# JACart.net
KiCad netlist of a schematic drawn in EAGLE
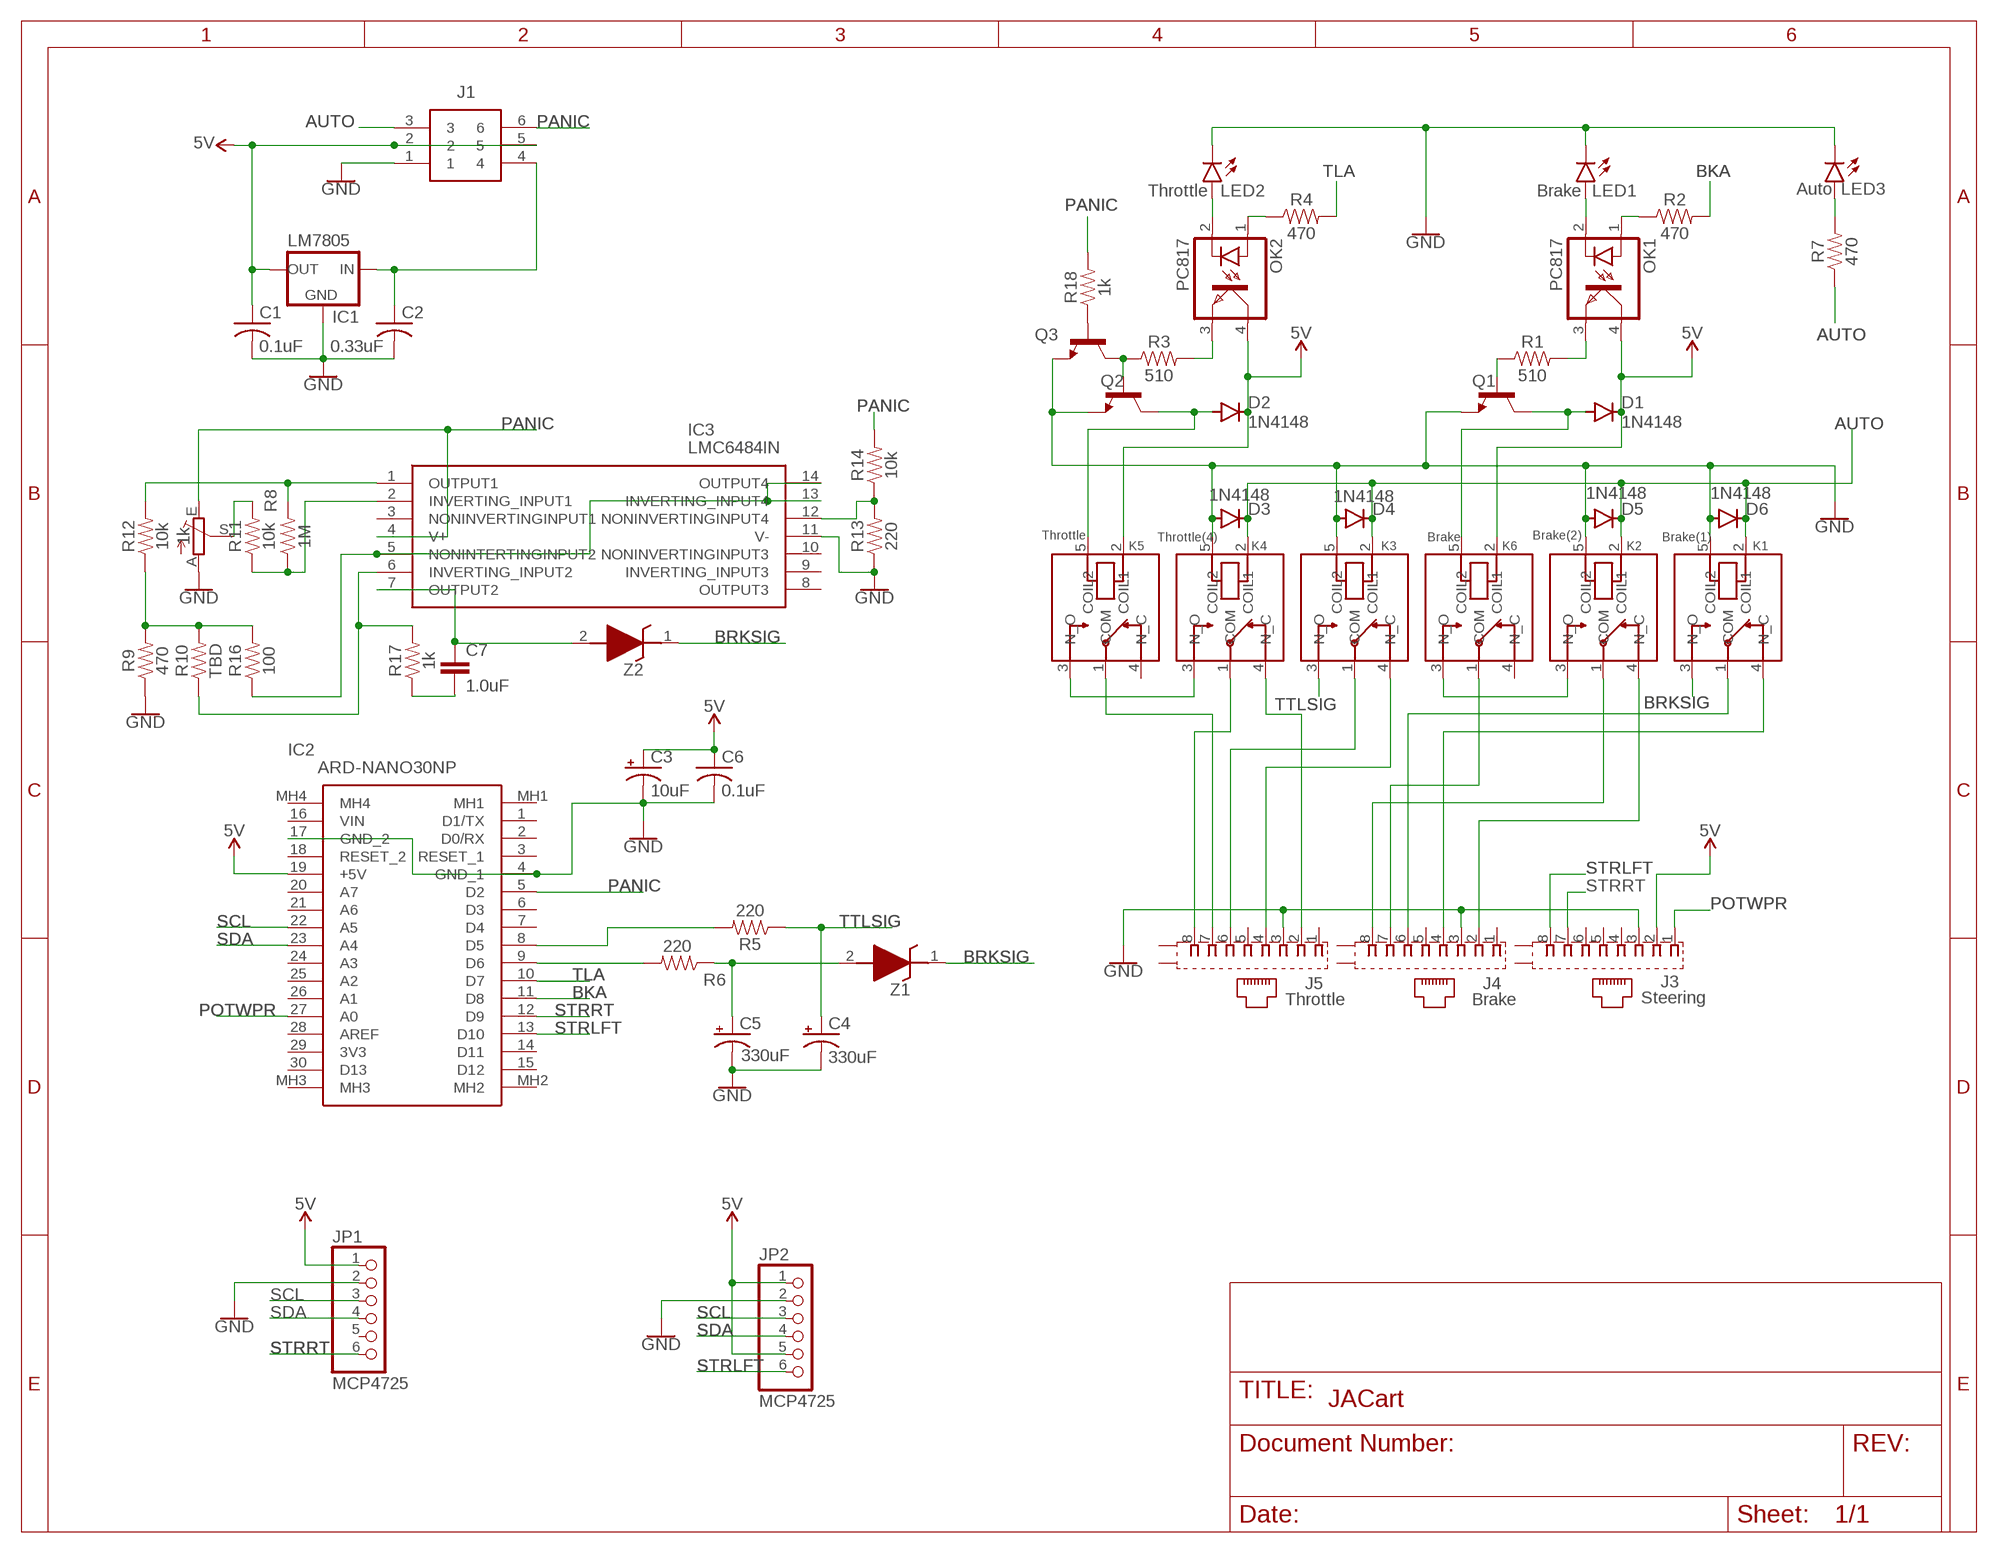
[diagram p0: schematic, sheet 1]

(export (version "E")
  (design (tool "Eeschema 10.0.6"))
  (components
    (comp (ref "C1")
      (value "0.1uF")
      (footprint "eagle-import:C050-024X044")
      (libsource (lib "eagle-import") (part "C-US050-024X044"))
    )
    (comp (ref "C2")
      (value "0.33uF")
      (footprint "eagle-import:C050-024X044")
      (libsource (lib "eagle-import") (part "C-US050-024X044"))
    )
    (comp (ref "C3")
      (value "10uF")
      (footprint "eagle-import:CPOL-RADIAL-2.5MM-5MM")
      (libsource (lib "eagle-import") (part "10UF-POLAR-RADIAL-2.5MM-25V-20%"))
    )
    (comp (ref "C4")
      (value "330uF")
      (footprint "eagle-import:PANASONIC_A")
      (libsource (lib "eagle-import") (part "330UF-PA"))
    )
    (comp (ref "C5")
      (value "330uF")
      (footprint "eagle-import:PANASONIC_A")
      (libsource (lib "eagle-import") (part "330UF-PA"))
    )
    (comp (ref "C6")
      (value "0.1uF")
      (footprint "eagle-import:C050-024X044")
      (fields (field (name "C6") "0.1uF"))
      (libsource (lib "eagle-import") (part "C-US050-024X044"))
    )
    (comp (ref "C7")
      (value "1.0uF")
      (footprint "eagle-import:CAP-PTH-SMALL-KIT")
      (libsource (lib "eagle-import") (part "0.1UF-KIT-EZ-50V-20%"))
    )
    (comp (ref "D1")
      (value "1N4148")
      (footprint "eagle-import:DO35-7")
      (libsource (lib "eagle-import") (part "1N4148DO35-7"))
    )
    (comp (ref "D2")
      (value "1N4148")
      (footprint "eagle-import:DO35-7")
      (libsource (lib "eagle-import") (part "1N4148DO35-7"))
    )
    (comp (ref "D3")
      (value "1N4148")
      (footprint "eagle-import:DO35-7")
      (libsource (lib "eagle-import") (part "1N4148DO35-7"))
    )
    (comp (ref "D4")
      (value "1N4148")
      (footprint "eagle-import:DO35-7")
      (libsource (lib "eagle-import") (part "1N4148DO35-7"))
    )
    (comp (ref "D5")
      (value "1N4148")
      (footprint "eagle-import:DO35-7")
      (libsource (lib "eagle-import") (part "1N4148DO35-7"))
    )
    (comp (ref "D6")
      (value "1N4148")
      (footprint "eagle-import:DO35-7")
      (libsource (lib "eagle-import") (part "1N4148DO35-7"))
    )
    (comp (ref "IC1")
      (value "LM7805")
      (footprint "eagle-import:78XXS")
      (libsource (lib "eagle-import") (part "7805-VR"))
    )
    (comp (ref "IC2")
      (value "ARD-NANO30NP")
      (footprint "eagle-import:ARDNANO30NP")
      (fields (field (name "MOUSER_PART_NUMBER") "992-ARD-NANO30NP"))
      (libsource (lib "eagle-import") (part "ARD-NANO30NP"))
    )
    (comp (ref "IC3")
      (value "LMC6484IN")
      (footprint "eagle-import:DIP794W56P254L1905H533Q14N")
      (fields (field (name "MOUSER_PART_NUMBER") "926-LMC6484IN"))
      (libsource (lib "eagle-import") (part "LMC6484IN"))
    )
    (comp (ref "J1")
      (value "39-30-1060")
      (footprint "eagle-import:39-30-1060_1")
      (fields (field (name "MOUSER_PART_NUMBER") "538-39-30-1060"))
      (libsource (lib "eagle-import") (part "39-30-1060"))
    )
    (comp (ref "J3")
      (value "Steering")
      (footprint "eagle-import:GLX-S-88M")
      (libsource (lib "eagle-import") (part "RJ45-RTANGL"))
    )
    (comp (ref "J4")
      (value "Brake")
      (footprint "eagle-import:GLX-S-88M")
      (fields (field (name "MF") "J4"))
      (libsource (lib "eagle-import") (part "RJ45-RTANGL"))
    )
    (comp (ref "J5")
      (value "Throttle")
      (footprint "eagle-import:GLX-S-88M")
      (libsource (lib "eagle-import") (part "RJ45-RTANGL"))
    )
    (comp (ref "JP1")
      (value "MCP4725")
      (footprint "eagle-import:1X06_ROUND_70")
      (libsource (lib "eagle-import") (part "HEADER-1X670MIL"))
    )
    (comp (ref "JP2")
      (value "MCP4725")
      (footprint "eagle-import:1X06_ROUND_70")
      (libsource (lib "eagle-import") (part "HEADER-1X670MIL"))
    )
    (comp (ref "K1")
      (value "Brake(1)")
      (footprint "eagle-import:RELAY_JS1-5V-F")
      (fields (field (name "MF") "Panasonic Electric") (field (name "MP") "JS1-5V-F"))
      (libsource (lib "eagle-import") (part "RELAY-SPDT"))
    )
    (comp (ref "K2")
      (value "Brake(2)")
      (footprint "eagle-import:RELAY_JS1-5V-F")
      (fields (field (name "MF") "Panasonic Electric") (field (name "MP") "JS1-5V-F"))
      (libsource (lib "eagle-import") (part "RELAY-SPDT"))
    )
    (comp (ref "K3")
      (value "Throttle(3)")
      (footprint "eagle-import:RELAY_JS1-5V-F")
      (fields (field (name "MF") "Panasonic Electric") (field (name "MP") "JS1-5V-F"))
      (libsource (lib "eagle-import") (part "RELAY-SPDT"))
    )
    (comp (ref "K4")
      (value "Throttle(4)")
      (footprint "eagle-import:RELAY_JS1-5V-F")
      (fields (field (name "MF") "Panasonic Electric") (field (name "MP") "JS1-5V-F"))
      (libsource (lib "eagle-import") (part "RELAY-SPDT"))
    )
    (comp (ref "K5")
      (value "Throttle")
      (footprint "eagle-import:RELAY_JS1-5V-F")
      (fields (field (name "MF") "Panasonic Electric") (field (name "MP") "JS1-5V-F"))
      (libsource (lib "eagle-import") (part "RELAY-SPDT"))
    )
    (comp (ref "K6")
      (value "Brake")
      (footprint "eagle-import:RELAY_JS1-5V-F")
      (fields (field (name "MF") "Panasonic Electric") (field (name "MP") "JS1-5V-F"))
      (libsource (lib "eagle-import") (part "RELAY-SPDT"))
    )
    (comp (ref "LED1")
      (value "Brake")
      (footprint "eagle-import:LED_5MM")
      (libsource (lib "eagle-import") (part "LED5MM"))
    )
    (comp (ref "LED2")
      (value "Throttle")
      (footprint "eagle-import:LED_5MM")
      (libsource (lib "eagle-import") (part "LED5MM"))
    )
    (comp (ref "LED3")
      (value "Auto")
      (footprint "eagle-import:LED_5MM")
      (libsource (lib "eagle-import") (part "LED5MM"))
    )
    (comp (ref "OK1")
      (value "PC817")
      (footprint "eagle-import:DIL04")
      (fields (field (name "MPN") "PC817X4J000F"))
      (libsource (lib "eagle-import") (part "PC817"))
    )
    (comp (ref "OK2")
      (value "PC817")
      (footprint "eagle-import:DIL04")
      (fields (field (name "MPN") "PC817X4J000F"))
      (libsource (lib "eagle-import") (part "PC817"))
    )
    (comp (ref "Q1")
      (value "2N3904")
      (footprint "eagle-import:TO92")
      (libsource (lib "eagle-import") (part "2N3904"))
    )
    (comp (ref "Q2")
      (value "2N3904")
      (footprint "eagle-import:TO92")
      (libsource (lib "eagle-import") (part "2N3904"))
    )
    (comp (ref "Q3")
      (value "2N3904")
      (footprint "eagle-import:TO92")
      (libsource (lib "eagle-import") (part "2N3904"))
    )
    (comp (ref "R1")
      (value "510")
      (footprint "eagle-import:AXIAL-0.3")
      (libsource (lib "eagle-import") (part "RESISTORAXIAL-0.3"))
    )
    (comp (ref "R2")
      (value "470")
      (footprint "eagle-import:AXIAL-0.3")
      (libsource (lib "eagle-import") (part "RESISTORAXIAL-0.3"))
    )
    (comp (ref "R3")
      (value "510")
      (footprint "eagle-import:AXIAL-0.3")
      (libsource (lib "eagle-import") (part "RESISTORAXIAL-0.3"))
    )
    (comp (ref "R4")
      (value "470")
      (footprint "eagle-import:AXIAL-0.3")
      (libsource (lib "eagle-import") (part "RESISTORAXIAL-0.3"))
    )
    (comp (ref "R5")
      (value "220")
      (footprint "eagle-import:AXIAL-0.3")
      (libsource (lib "eagle-import") (part "RESISTORAXIAL-0.3"))
    )
    (comp (ref "R6")
      (value "220")
      (footprint "eagle-import:AXIAL-0.3")
      (libsource (lib "eagle-import") (part "RESISTORAXIAL-0.3"))
    )
    (comp (ref "R7")
      (value "470")
      (footprint "eagle-import:AXIAL-0.3")
      (libsource (lib "eagle-import") (part "RESISTORAXIAL-0.3"))
    )
    (comp (ref "R8")
      (value "1M")
      (footprint "eagle-import:AXIAL-0.3")
      (libsource (lib "eagle-import") (part "RESISTORAXIAL-0.3"))
    )
    (comp (ref "R9")
      (value "470")
      (footprint "eagle-import:AXIAL-0.3")
      (libsource (lib "eagle-import") (part "RESISTORAXIAL-0.3"))
    )
    (comp (ref "R10")
      (value "TBD")
      (footprint "eagle-import:AXIAL-0.3")
      (libsource (lib "eagle-import") (part "RESISTORAXIAL-0.3"))
    )
    (comp (ref "R11")
      (value "10k")
      (footprint "eagle-import:AXIAL-0.3")
      (libsource (lib "eagle-import") (part "RESISTORAXIAL-0.3"))
    )
    (comp (ref "R12")
      (value "10k")
      (footprint "eagle-import:AXIAL-0.3")
      (libsource (lib "eagle-import") (part "RESISTORAXIAL-0.3"))
    )
    (comp (ref "R13")
      (value "220")
      (footprint "eagle-import:AXIAL-0.3")
      (libsource (lib "eagle-import") (part "RESISTORAXIAL-0.3"))
    )
    (comp (ref "R14")
      (value "10k")
      (footprint "eagle-import:AXIAL-0.3")
      (libsource (lib "eagle-import") (part "RESISTORAXIAL-0.3"))
    )
    (comp (ref "R15")
      (value "1k")
      (footprint "eagle-import:RJ9W")
      (libsource (lib "eagle-import") (part "TRIM_EU-RJ9W"))
    )
    (comp (ref "R16")
      (value "100")
      (footprint "eagle-import:AXIAL-0.3")
      (libsource (lib "eagle-import") (part "RESISTORAXIAL-0.3"))
    )
    (comp (ref "R17")
      (value "1k")
      (footprint "eagle-import:AXIAL-0.3")
      (libsource (lib "eagle-import") (part "RESISTORAXIAL-0.3"))
    )
    (comp (ref "R18")
      (value "1k")
      (footprint "eagle-import:AXIAL-0.3")
      (libsource (lib "eagle-import") (part "RESISTORAXIAL-0.3"))
    )
    (comp (ref "Z1")
      (value "BAT85S-TR")
      (footprint "eagle-import:DIOAD950W60L350D150")
      (fields (field (name "MOUSER_PART_NUMBER") "78-BAT85S"))
      (libsource (lib "eagle-import") (part "BAT85S-TR"))
    )
    (comp (ref "Z2")
      (value "BAT85S-TR")
      (footprint "eagle-import:DIOAD950W60L350D150")
      (fields (field (name "MOUSER_PART_NUMBER") "78-BAT85S"))
      (libsource (lib "eagle-import") (part "BAT85S-TR"))
    )
  )
  (nets
    (net (code "1") (name "/AUTO") (class "Default")
      (node (ref "D3") (pin "C") (pinfunction "C_C") (pintype "passive"))
      (node (ref "D4") (pin "C") (pinfunction "C_C") (pintype "passive"))
      (node (ref "D5") (pin "C") (pinfunction "C_C") (pintype "passive"))
      (node (ref "D6") (pin "C") (pinfunction "C_C") (pintype "passive"))
      (node (ref "J1") (pin "3") (pinfunction "3_3") (pintype "bidirectional"))
      (node (ref "K1") (pin "2") (pinfunction "COIL1_2") (pintype "passive"))
      (node (ref "K2") (pin "2") (pinfunction "COIL1_2") (pintype "passive"))
      (node (ref "K3") (pin "2") (pinfunction "COIL1_2") (pintype "passive"))
      (node (ref "K4") (pin "2") (pinfunction "COIL1_2") (pintype "passive"))
      (node (ref "R7") (pin "P$1") (pinfunction "1_P$1") (pintype "passive"))
    )
    (net (code "2") (name "/BKA") (class "Default")
      (node (ref "IC2") (pin "11") (pinfunction "D8_11") (pintype "bidirectional"))
      (node (ref "R2") (pin "P$2") (pinfunction "2_P$2") (pintype "passive"))
    )
    (net (code "3") (name "/BRKSIG") (class "Default")
      (node (ref "K1") (pin "3") (pinfunction "N_O_3") (pintype "passive"))
      (node (ref "Z1") (pin "1") (pinfunction "K_1") (pintype "bidirectional"))
      (node (ref "Z2") (pin "1") (pinfunction "K_1") (pintype "bidirectional"))
    )
    (net (code "4") (name "/PANIC") (class "Default")
      (node (ref "IC2") (pin "5") (pinfunction "D2_5") (pintype "bidirectional"))
      (node (ref "IC3") (pin "4") (pinfunction "V+_4") (pintype "bidirectional"))
      (node (ref "J1") (pin "6") (pinfunction "6_6") (pintype "bidirectional"))
      (node (ref "R14") (pin "P$2") (pinfunction "2_P$2") (pintype "passive"))
      (node (ref "R15") (pin "E") (pinfunction "E_E") (pintype "passive"))
      (node (ref "R18") (pin "P$2") (pinfunction "2_P$2") (pintype "passive"))
    )
    (net (code "5") (name "/POTWPR") (class "Default")
      (node (ref "IC2") (pin "27") (pinfunction "A0_27") (pintype "bidirectional"))
      (node (ref "J3") (pin "1") (pinfunction "1_1") (pintype "passive"))
    )
    (net (code "6") (name "/SCL") (class "Default")
      (node (ref "IC2") (pin "22") (pinfunction "A5_22") (pintype "bidirectional"))
      (node (ref "JP1") (pin "3") (pinfunction "3_3") (pintype "passive"))
      (node (ref "JP2") (pin "3") (pinfunction "3_3") (pintype "passive"))
    )
    (net (code "7") (name "/SDA") (class "Default")
      (node (ref "IC2") (pin "23") (pinfunction "A4_23") (pintype "bidirectional"))
      (node (ref "JP1") (pin "4") (pinfunction "4_4") (pintype "passive"))
      (node (ref "JP2") (pin "4") (pinfunction "4_4") (pintype "passive"))
    )
    (net (code "8") (name "/STRLFT") (class "Default")
      (node (ref "IC2") (pin "13") (pinfunction "D10_13") (pintype "bidirectional"))
      (node (ref "J3") (pin "8") (pinfunction "8_8") (pintype "passive"))
      (node (ref "JP2") (pin "6") (pinfunction "6_6") (pintype "passive"))
    )
    (net (code "9") (name "/STRRT") (class "Default")
      (node (ref "IC2") (pin "12") (pinfunction "D9_12") (pintype "bidirectional"))
      (node (ref "J3") (pin "7") (pinfunction "7_7") (pintype "passive"))
      (node (ref "JP1") (pin "6") (pinfunction "6_6") (pintype "passive"))
    )
    (net (code "10") (name "/TLA") (class "Default")
      (node (ref "IC2") (pin "10") (pinfunction "D7_10") (pintype "bidirectional"))
      (node (ref "R4") (pin "P$2") (pinfunction "2_P$2") (pintype "passive"))
    )
    (net (code "11") (name "/TTLSIG") (class "Default")
      (node (ref "C4") (pin "+") (pinfunction "+_+") (pintype "passive"))
      (node (ref "K3") (pin "3") (pinfunction "N_O_3") (pintype "passive"))
      (node (ref "R5") (pin "P$1") (pinfunction "1_P$1") (pintype "passive"))
    )
    (net (code "12") (name "5V") (class "Default")
      (node (ref "C1") (pin "1") (pinfunction "1_1") (pintype "passive"))
      (node (ref "C3") (pin "1") (pinfunction "+_1") (pintype "passive"))
      (node (ref "C6") (pin "1") (pinfunction "1_1") (pintype "passive"))
      (node (ref "D1") (pin "C") (pinfunction "C_C") (pintype "passive"))
      (node (ref "D2") (pin "C") (pinfunction "C_C") (pintype "passive"))
      (node (ref "IC1") (pin "OUT") (pinfunction "OUT_OUT") (pintype "passive"))
      (node (ref "IC2") (pin "19") (pinfunction "+5V_19") (pintype "bidirectional"))
      (node (ref "J1") (pin "2") (pinfunction "2_2") (pintype "bidirectional"))
      (node (ref "J1") (pin "5") (pinfunction "5_5") (pintype "bidirectional"))
      (node (ref "J3") (pin "2") (pinfunction "2_2") (pintype "passive"))
      (node (ref "JP1") (pin "1") (pinfunction "1_1") (pintype "passive"))
      (node (ref "JP2") (pin "1") (pinfunction "1_1") (pintype "passive"))
      (node (ref "JP2") (pin "5") (pinfunction "5_5") (pintype "passive"))
      (node (ref "K5") (pin "2") (pinfunction "COIL1_2") (pintype "passive"))
      (node (ref "K6") (pin "2") (pinfunction "COIL1_2") (pintype "passive"))
      (node (ref "OK1") (pin "4") (pinfunction "COL_4") (pintype "passive"))
      (node (ref "OK2") (pin "4") (pinfunction "COL_4") (pintype "passive"))
    )
    (net (code "13") (name "GND") (class "Default")
      (node (ref "C1") (pin "2") (pinfunction "2_2") (pintype "passive"))
      (node (ref "C2") (pin "2") (pinfunction "2_2") (pintype "passive"))
      (node (ref "C3") (pin "2") (pinfunction "-_2") (pintype "passive"))
      (node (ref "C4") (pin "-") (pinfunction "-_-") (pintype "passive"))
      (node (ref "C5") (pin "-") (pinfunction "-_-") (pintype "passive"))
      (node (ref "C6") (pin "2") (pinfunction "2_2") (pintype "passive"))
      (node (ref "D3") (pin "A") (pinfunction "A_A") (pintype "passive"))
      (node (ref "D4") (pin "A") (pinfunction "A_A") (pintype "passive"))
      (node (ref "D5") (pin "A") (pinfunction "A_A") (pintype "passive"))
      (node (ref "D6") (pin "A") (pinfunction "A_A") (pintype "passive"))
      (node (ref "IC1") (pin "GND") (pinfunction "GND_GND") (pintype "input"))
      (node (ref "IC2") (pin "17") (pinfunction "GND_2_17") (pintype "bidirectional"))
      (node (ref "IC2") (pin "4") (pinfunction "GND_1_4") (pintype "bidirectional"))
      (node (ref "IC3") (pin "11") (pinfunction "V-_11") (pintype "bidirectional"))
      (node (ref "J1") (pin "1") (pinfunction "1_1") (pintype "bidirectional"))
      (node (ref "J3") (pin "3") (pinfunction "3_3") (pintype "passive"))
      (node (ref "J4") (pin "3") (pinfunction "3_3") (pintype "passive"))
      (node (ref "J5") (pin "3") (pinfunction "3_3") (pintype "passive"))
      (node (ref "JP1") (pin "2") (pinfunction "2_2") (pintype "passive"))
      (node (ref "JP2") (pin "2") (pinfunction "2_2") (pintype "passive"))
      (node (ref "K1") (pin "5") (pinfunction "COIL2_5") (pintype "passive"))
      (node (ref "K2") (pin "5") (pinfunction "COIL2_5") (pintype "passive"))
      (node (ref "K3") (pin "5") (pinfunction "COIL2_5") (pintype "passive"))
      (node (ref "K4") (pin "5") (pinfunction "COIL2_5") (pintype "passive"))
      (node (ref "LED1") (pin "K") (pinfunction "C_K") (pintype "passive"))
      (node (ref "LED2") (pin "K") (pinfunction "C_K") (pintype "passive"))
      (node (ref "LED3") (pin "K") (pinfunction "C_K") (pintype "passive"))
      (node (ref "Q1") (pin "3") (pinfunction "E_3") (pintype "passive"))
      (node (ref "Q2") (pin "3") (pinfunction "E_3") (pintype "passive"))
      (node (ref "Q3") (pin "3") (pinfunction "E_3") (pintype "passive"))
      (node (ref "R13") (pin "P$1") (pinfunction "1_P$1") (pintype "passive"))
      (node (ref "R15") (pin "A") (pinfunction "A_A") (pintype "passive"))
      (node (ref "R9") (pin "P$1") (pinfunction "1_P$1") (pintype "passive"))
    )
    (net (code "14") (name "Net-(C2-Pad1)") (class "Default")
      (node (ref "C2") (pin "1") (pinfunction "1_1") (pintype "passive"))
      (node (ref "IC1") (pin "IN") (pinfunction "IN_IN") (pintype "input"))
      (node (ref "J1") (pin "4") (pinfunction "4_4") (pintype "bidirectional"))
    )
    (net (code "15") (name "Net-(IC2-D5)") (class "Default")
      (node (ref "IC2") (pin "8") (pinfunction "D5_8") (pintype "bidirectional"))
      (node (ref "R5") (pin "P$2") (pinfunction "2_P$2") (pintype "passive"))
    )
    (net (code "16") (name "Net-(IC2-D6)") (class "Default")
      (node (ref "IC2") (pin "9") (pinfunction "D6_9") (pintype "bidirectional"))
      (node (ref "R6") (pin "P$2") (pinfunction "2_P$2") (pintype "passive"))
    )
    (net (code "17") (name "Net-(IC3-INVERTING_INPUT1)") (class "Default")
      (node (ref "IC3") (pin "2") (pinfunction "INVERTING_INPUT1_2") (pintype "bidirectional"))
      (node (ref "R11") (pin "P$1") (pinfunction "1_P$1") (pintype "passive"))
      (node (ref "R8") (pin "P$1") (pinfunction "1_P$1") (pintype "passive"))
    )
    (net (code "18") (name "Net-(IC3-INVERTING_INPUT2)") (class "Default")
      (node (ref "IC3") (pin "6") (pinfunction "INVERTING_INPUT2_6") (pintype "bidirectional"))
      (node (ref "R10") (pin "P$1") (pinfunction "1_P$1") (pintype "passive"))
      (node (ref "R17") (pin "P$2") (pinfunction "2_P$2") (pintype "passive"))
    )
    (net (code "19") (name "Net-(IC3-INVERTING_INPUT4)") (class "Default")
      (node (ref "IC3") (pin "13") (pinfunction "INVERTING_INPUT4_13") (pintype "bidirectional"))
      (node (ref "IC3") (pin "14") (pinfunction "OUTPUT4_14") (pintype "bidirectional"))
      (node (ref "IC3") (pin "5") (pinfunction "NONINTERTINGINPUT2_5") (pintype "bidirectional"))
      (node (ref "R16") (pin "P$1") (pinfunction "1_P$1") (pintype "passive"))
    )
    (net (code "20") (name "Net-(IC3-NONINVERTINGINPUT4)") (class "Default")
      (node (ref "IC3") (pin "12") (pinfunction "NONINVERTINGINPUT4_12") (pintype "bidirectional"))
      (node (ref "R13") (pin "P$2") (pinfunction "2_P$2") (pintype "passive"))
      (node (ref "R14") (pin "P$1") (pinfunction "1_P$1") (pintype "passive"))
    )
    (net (code "21") (name "Net-(IC3-OUTPUT1)") (class "Default")
      (node (ref "IC3") (pin "1") (pinfunction "OUTPUT1_1") (pintype "bidirectional"))
      (node (ref "R12") (pin "P$2") (pinfunction "2_P$2") (pintype "passive"))
      (node (ref "R8") (pin "P$2") (pinfunction "2_P$2") (pintype "passive"))
    )
    (net (code "22") (name "Net-(IC3-OUTPUT2)") (class "Default")
      (node (ref "C7") (pin "1") (pinfunction "1_1") (pintype "passive"))
      (node (ref "IC3") (pin "7") (pinfunction "OUTPUT2_7") (pintype "bidirectional"))
      (node (ref "Z2") (pin "2") (pinfunction "A_2") (pintype "bidirectional"))
    )
    (net (code "23") (name "Net-(K1-COM)") (class "Default")
      (node (ref "J4") (pin "6") (pinfunction "6_6") (pintype "passive"))
      (node (ref "K1") (pin "1") (pinfunction "COM_1") (pintype "passive"))
    )
    (net (code "24") (name "Net-(K1-N_C)") (class "Default")
      (node (ref "J4") (pin "4") (pinfunction "4_4") (pintype "passive"))
      (node (ref "K1") (pin "4") (pinfunction "N_C_4") (pintype "passive"))
    )
    (net (code "25") (name "Net-(K2-COM)") (class "Default")
      (node (ref "J4") (pin "8") (pinfunction "8_8") (pintype "passive"))
      (node (ref "K2") (pin "1") (pinfunction "COM_1") (pintype "passive"))
    )
    (net (code "26") (name "Net-(K2-N_C)") (class "Default")
      (node (ref "J4") (pin "2") (pinfunction "2_2") (pintype "passive"))
      (node (ref "K2") (pin "4") (pinfunction "N_C_4") (pintype "passive"))
    )
    (net (code "27") (name "Net-(K2-N_O)") (class "Default")
      (node (ref "K2") (pin "3") (pinfunction "N_O_3") (pintype "passive"))
      (node (ref "K6") (pin "3") (pinfunction "N_O_3") (pintype "passive"))
    )
    (net (code "28") (name "Net-(K3-COM)") (class "Default")
      (node (ref "J5") (pin "6") (pinfunction "6_6") (pintype "passive"))
      (node (ref "K3") (pin "1") (pinfunction "COM_1") (pintype "passive"))
    )
    (net (code "29") (name "Net-(K3-N_C)") (class "Default")
      (node (ref "J5") (pin "4") (pinfunction "4_4") (pintype "passive"))
      (node (ref "K3") (pin "4") (pinfunction "N_C_4") (pintype "passive"))
    )
    (net (code "30") (name "Net-(K4-COM)") (class "Default")
      (node (ref "J5") (pin "8") (pinfunction "8_8") (pintype "passive"))
      (node (ref "K4") (pin "1") (pinfunction "COM_1") (pintype "passive"))
    )
    (net (code "31") (name "Net-(K4-N_C)") (class "Default")
      (node (ref "J5") (pin "2") (pinfunction "2_2") (pintype "passive"))
      (node (ref "K4") (pin "4") (pinfunction "N_C_4") (pintype "passive"))
    )
    (net (code "32") (name "Net-(K4-N_O)") (class "Default")
      (node (ref "K4") (pin "3") (pinfunction "N_O_3") (pintype "passive"))
      (node (ref "K5") (pin "3") (pinfunction "N_O_3") (pintype "passive"))
    )
    (net (code "33") (name "Net-(K5-COIL2)") (class "Default")
      (node (ref "D2") (pin "A") (pinfunction "A_A") (pintype "passive"))
      (node (ref "K5") (pin "5") (pinfunction "COIL2_5") (pintype "passive"))
      (node (ref "Q2") (pin "1") (pinfunction "C_1") (pintype "passive"))
    )
    (net (code "34") (name "Net-(K5-COM)") (class "Default")
      (node (ref "J5") (pin "7") (pinfunction "7_7") (pintype "passive"))
      (node (ref "K5") (pin "1") (pinfunction "COM_1") (pintype "passive"))
    )
    (net (code "35") (name "Net-(K6-COIL2)") (class "Default")
      (node (ref "D1") (pin "A") (pinfunction "A_A") (pintype "passive"))
      (node (ref "K6") (pin "5") (pinfunction "COIL2_5") (pintype "passive"))
      (node (ref "Q1") (pin "1") (pinfunction "C_1") (pintype "passive"))
    )
    (net (code "36") (name "Net-(K6-COM)") (class "Default")
      (node (ref "J4") (pin "7") (pinfunction "7_7") (pintype "passive"))
      (node (ref "K6") (pin "1") (pinfunction "COM_1") (pintype "passive"))
    )
    (net (code "37") (name "Net-(OK1-A)") (class "Default")
      (node (ref "OK1") (pin "1") (pinfunction "A_1") (pintype "passive"))
      (node (ref "R2") (pin "P$1") (pinfunction "1_P$1") (pintype "passive"))
    )
    (net (code "38") (name "Net-(OK1-C)") (class "Default")
      (node (ref "LED1") (pin "A") (pinfunction "A_A") (pintype "passive"))
      (node (ref "OK1") (pin "2") (pinfunction "C_2") (pintype "passive"))
    )
    (net (code "39") (name "Net-(OK1-EMIT)") (class "Default")
      (node (ref "OK1") (pin "3") (pinfunction "EMIT_3") (pintype "passive"))
      (node (ref "R1") (pin "P$2") (pinfunction "2_P$2") (pintype "passive"))
    )
    (net (code "40") (name "Net-(OK2-A)") (class "Default")
      (node (ref "OK2") (pin "1") (pinfunction "A_1") (pintype "passive"))
      (node (ref "R4") (pin "P$1") (pinfunction "1_P$1") (pintype "passive"))
    )
    (net (code "41") (name "Net-(OK2-C)") (class "Default")
      (node (ref "LED2") (pin "A") (pinfunction "A_A") (pintype "passive"))
      (node (ref "OK2") (pin "2") (pinfunction "C_2") (pintype "passive"))
    )
    (net (code "42") (name "Net-(OK2-EMIT)") (class "Default")
      (node (ref "OK2") (pin "3") (pinfunction "EMIT_3") (pintype "passive"))
      (node (ref "R3") (pin "P$2") (pinfunction "2_P$2") (pintype "passive"))
    )
    (net (code "43") (name "Net-(Q1-B)") (class "Default")
      (node (ref "Q1") (pin "2") (pinfunction "B_2") (pintype "passive"))
      (node (ref "R1") (pin "P$1") (pinfunction "1_P$1") (pintype "passive"))
    )
    (net (code "44") (name "Net-(Q2-B)") (class "Default")
      (node (ref "Q2") (pin "2") (pinfunction "B_2") (pintype "passive"))
      (node (ref "Q3") (pin "1") (pinfunction "C_1") (pintype "passive"))
      (node (ref "R3") (pin "P$1") (pinfunction "1_P$1") (pintype "passive"))
    )
    (net (code "45") (name "Net-(Q3-B)") (class "Default")
      (node (ref "Q3") (pin "2") (pinfunction "B_2") (pintype "passive"))
      (node (ref "R18") (pin "P$1") (pinfunction "1_P$1") (pintype "passive"))
    )
    (net (code "46") (name "Net-(R6-1)") (class "Default")
      (node (ref "C5") (pin "+") (pinfunction "+_+") (pintype "passive"))
      (node (ref "R6") (pin "P$1") (pinfunction "1_P$1") (pintype "passive"))
      (node (ref "Z1") (pin "2") (pinfunction "A_2") (pintype "bidirectional"))
    )
    (net (code "47") (name "Net-(R7-2)") (class "Default")
      (node (ref "LED3") (pin "A") (pinfunction "A_A") (pintype "passive"))
      (node (ref "R7") (pin "P$2") (pinfunction "2_P$2") (pintype "passive"))
    )
    (net (code "48") (name "Net-(R10-2)") (class "Default")
      (node (ref "R10") (pin "P$2") (pinfunction "2_P$2") (pintype "passive"))
      (node (ref "R12") (pin "P$1") (pinfunction "1_P$1") (pintype "passive"))
      (node (ref "R16") (pin "P$2") (pinfunction "2_P$2") (pintype "passive"))
      (node (ref "R9") (pin "P$2") (pinfunction "2_P$2") (pintype "passive"))
    )
    (net (code "49") (name "Net-(R11-2)") (class "Default")
      (node (ref "R11") (pin "P$2") (pinfunction "2_P$2") (pintype "passive"))
      (node (ref "R15") (pin "S") (pinfunction "S_S") (pintype "passive"))
    )
    (net (code "50") (name "Net-(R17-1)") (class "Default")
      (node (ref "C7") (pin "2") (pinfunction "2_2") (pintype "passive"))
      (node (ref "R17") (pin "P$1") (pinfunction "1_P$1") (pintype "passive"))
    )
    (net (code "51") (name "unconnected-(IC2-3V3-Pad29)") (class "Default")
      (node (ref "IC2") (pin "29") (pinfunction "3V3_29") (pintype "bidirectional"))
    )
    (net (code "52") (name "unconnected-(IC2-A1-Pad26)") (class "Default")
      (node (ref "IC2") (pin "26") (pinfunction "A1_26") (pintype "bidirectional"))
    )
    (net (code "53") (name "unconnected-(IC2-A2-Pad25)") (class "Default")
      (node (ref "IC2") (pin "25") (pinfunction "A2_25") (pintype "bidirectional"))
    )
    (net (code "54") (name "unconnected-(IC2-A3-Pad24)") (class "Default")
      (node (ref "IC2") (pin "24") (pinfunction "A3_24") (pintype "bidirectional"))
    )
    (net (code "55") (name "unconnected-(IC2-A6-Pad21)") (class "Default")
      (node (ref "IC2") (pin "21") (pinfunction "A6_21") (pintype "bidirectional"))
    )
    (net (code "56") (name "unconnected-(IC2-A7-Pad20)") (class "Default")
      (node (ref "IC2") (pin "20") (pinfunction "A7_20") (pintype "bidirectional"))
    )
    (net (code "57") (name "unconnected-(IC2-AREF-Pad28)") (class "Default")
      (node (ref "IC2") (pin "28") (pinfunction "AREF_28") (pintype "bidirectional"))
    )
    (net (code "58") (name "unconnected-(IC2-D0{slash}RX-Pad2)") (class "Default")
      (node (ref "IC2") (pin "2") (pinfunction "D0/RX_2") (pintype "bidirectional"))
    )
    (net (code "59") (name "unconnected-(IC2-D1{slash}TX-Pad1)") (class "Default")
      (node (ref "IC2") (pin "1") (pinfunction "D1/TX_1") (pintype "bidirectional"))
    )
    (net (code "60") (name "unconnected-(IC2-D3-Pad6)") (class "Default")
      (node (ref "IC2") (pin "6") (pinfunction "D3_6") (pintype "bidirectional"))
    )
    (net (code "61") (name "unconnected-(IC2-D4-Pad7)") (class "Default")
      (node (ref "IC2") (pin "7") (pinfunction "D4_7") (pintype "bidirectional"))
    )
    (net (code "62") (name "unconnected-(IC2-D11-Pad14)") (class "Default")
      (node (ref "IC2") (pin "14") (pinfunction "D11_14") (pintype "bidirectional"))
    )
    (net (code "63") (name "unconnected-(IC2-D12-Pad15)") (class "Default")
      (node (ref "IC2") (pin "15") (pinfunction "D12_15") (pintype "bidirectional"))
    )
    (net (code "64") (name "unconnected-(IC2-D13-Pad30)") (class "Default")
      (node (ref "IC2") (pin "30") (pinfunction "D13_30") (pintype "bidirectional"))
    )
    (net (code "65") (name "unconnected-(IC2-PadMH1)") (class "Default")
      (node (ref "IC2") (pin "MH1") (pinfunction "MH1_MH1") (pintype "bidirectional"))
    )
    (net (code "66") (name "unconnected-(IC2-PadMH2)") (class "Default")
      (node (ref "IC2") (pin "MH2") (pinfunction "MH2_MH2") (pintype "bidirectional"))
    )
    (net (code "67") (name "unconnected-(IC2-PadMH3)") (class "Default")
      (node (ref "IC2") (pin "MH3") (pinfunction "MH3_MH3") (pintype "bidirectional"))
    )
    (net (code "68") (name "unconnected-(IC2-PadMH4)") (class "Default")
      (node (ref "IC2") (pin "MH4") (pinfunction "MH4_MH4") (pintype "bidirectional"))
    )
    (net (code "69") (name "unconnected-(IC2-RESET_1-Pad3)") (class "Default")
      (node (ref "IC2") (pin "3") (pinfunction "RESET_1_3") (pintype "bidirectional"))
    )
    (net (code "70") (name "unconnected-(IC2-RESET_2-Pad18)") (class "Default")
      (node (ref "IC2") (pin "18") (pinfunction "RESET_2_18") (pintype "bidirectional"))
    )
    (net (code "71") (name "unconnected-(IC2-VIN-Pad16)") (class "Default")
      (node (ref "IC2") (pin "16") (pinfunction "VIN_16") (pintype "bidirectional"))
    )
    (net (code "72") (name "unconnected-(IC3-INVERTING_INPUT3-Pad9)") (class "Default")
      (node (ref "IC3") (pin "9") (pinfunction "INVERTING_INPUT3_9") (pintype "bidirectional"))
    )
    (net (code "73") (name "unconnected-(IC3-NONINVERTINGINPUT1-Pad3)") (class "Default")
      (node (ref "IC3") (pin "3") (pinfunction "NONINVERTINGINPUT1_3") (pintype "bidirectional"))
    )
    (net (code "74") (name "unconnected-(IC3-NONINVERTINGINPUT3-Pad10)") (class "Default")
      (node (ref "IC3") (pin "10") (pinfunction "NONINVERTINGINPUT3_10") (pintype "bidirectional"))
    )
    (net (code "75") (name "unconnected-(IC3-OUTPUT3-Pad8)") (class "Default")
      (node (ref "IC3") (pin "8") (pinfunction "OUTPUT3_8") (pintype "bidirectional"))
    )
    (net (code "76") (name "unconnected-(J3-Pad4)") (class "Default")
      (node (ref "J3") (pin "4") (pinfunction "4_4") (pintype "passive"))
    )
    (net (code "77") (name "unconnected-(J3-Pad5)") (class "Default")
      (node (ref "J3") (pin "5") (pinfunction "5_5") (pintype "passive"))
    )
    (net (code "78") (name "unconnected-(J3-Pad6)") (class "Default")
      (node (ref "J3") (pin "6") (pinfunction "6_6") (pintype "passive"))
    )
    (net (code "79") (name "unconnected-(J3-PadS1)") (class "Default")
      (node (ref "J3") (pin "S1") (pinfunction "S1_S1") (pintype "passive"))
    )
    (net (code "80") (name "unconnected-(J3-PadS2)") (class "Default")
      (node (ref "J3") (pin "S2") (pinfunction "S2_S2") (pintype "passive"))
    )
    (net (code "81") (name "unconnected-(J4-Pad1)") (class "Default")
      (node (ref "J4") (pin "1") (pinfunction "1_1") (pintype "passive"))
    )
    (net (code "82") (name "unconnected-(J4-Pad5)") (class "Default")
      (node (ref "J4") (pin "5") (pinfunction "5_5") (pintype "passive"))
    )
    (net (code "83") (name "unconnected-(J4-PadS1)") (class "Default")
      (node (ref "J4") (pin "S1") (pinfunction "S1_S1") (pintype "passive"))
    )
    (net (code "84") (name "unconnected-(J4-PadS2)") (class "Default")
      (node (ref "J4") (pin "S2") (pinfunction "S2_S2") (pintype "passive"))
    )
    (net (code "85") (name "unconnected-(J5-Pad1)") (class "Default")
      (node (ref "J5") (pin "1") (pinfunction "1_1") (pintype "passive"))
    )
    (net (code "86") (name "unconnected-(J5-Pad5)") (class "Default")
      (node (ref "J5") (pin "5") (pinfunction "5_5") (pintype "passive"))
    )
    (net (code "87") (name "unconnected-(J5-PadS1)") (class "Default")
      (node (ref "J5") (pin "S1") (pinfunction "S1_S1") (pintype "passive"))
    )
    (net (code "88") (name "unconnected-(J5-PadS2)") (class "Default")
      (node (ref "J5") (pin "S2") (pinfunction "S2_S2") (pintype "passive"))
    )
    (net (code "89") (name "unconnected-(JP1-Pad5)") (class "Default")
      (node (ref "JP1") (pin "5") (pinfunction "5_5") (pintype "passive"))
    )
    (net (code "90") (name "unconnected-(K5-N_C-Pad4)") (class "Default")
      (node (ref "K5") (pin "4") (pinfunction "N_C_4") (pintype "passive"))
    )
    (net (code "91") (name "unconnected-(K6-N_C-Pad4)") (class "Default")
      (node (ref "K6") (pin "4") (pinfunction "N_C_4") (pintype "passive"))
    )
  )
)
